# 5v_to_3_3v_convertor.net
KiCad netlist of a schematic drawn in Altium Designer
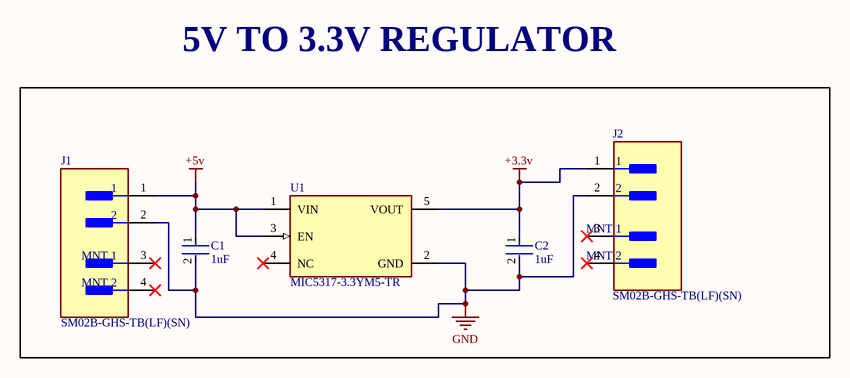
[diagram p0: 5v to 3.3v convertor.SchDoc]

(export (version "E")
  (design (tool "Eeschema 10.0.6"))
  (components
    (comp (ref "C1")
      (value "1uF")
      (footprint "FP-CC0805-0_85-MFG")
      (description "CAP CER 1UF 10V X7R 0805")
      (fields
        (field (name "MANUFACTURER") "Yageo")
        (field (name "OCTOPART") "https://octopart.com/cc0805kkx7r6bb105-yageo-42522859")
      )
      (libsource (lib "Altium Content Vault") (part "11868f565c42a9108669ba33697ecf6"))
    )
    (comp (ref "C2")
      (value "1uF")
      (footprint "FP-CC0805-0_85-MFG")
      (description "CAP CER 1UF 10V X7R 0805")
      (fields
        (field (name "MANUFACTURER") "Yageo")
        (field (name "OCTOPART") "https://octopart.com/cc0805kkx7r6bb105-yageo-42522859")
      )
      (libsource (lib "Altium Content Vault") (part "11868f565c42a9108669ba33697ecf6"))
    )
    (comp (ref "J1")
      (value "SM02B-GHS-TB(LF)(SN)")
      (footprint "FP-SM02B-GHS-TB_LF_SN-MFG")
      (description "CONN HEADER SMD R/A 2POS 1.25MM")
      (libsource (lib "Altium Content Vault") (part "56ec3178a87b3978bdc1b3682cd516a"))
    )
    (comp (ref "J2")
      (value "SM02B-GHS-TB(LF)(SN)")
      (footprint "FP-SM02B-GHS-TB_LF_SN-MFG")
      (description "CONN HEADER SMD R/A 2POS 1.25MM")
      (libsource (lib "") (part "56ec3178a87b3978bdc1b3682cd516a_1"))
    )
    (comp (ref "U1")
      (value "MIC5317-3.3YM5-TR")
      (footprint "FP-SOT23-5LD-PL-1-MFG")
      (description "IC REG LINEAR 3.3V 150MA SOT23-5")
      (libsource (lib "Altium Content Vault") (part "0a093dae7315cdc977fd108dde87457"))
    )
  )
  (nets
    (net (code "1") (name "+3.3v") (class "Default")
      (node (ref "C2") (pin "1") (pinfunction "1_1") (pintype "passive"))
      (node (ref "J2") (pin "1") (pinfunction "1_1") (pintype "passive"))
      (node (ref "U1") (pin "5") (pinfunction "VOUT_5") (pintype "power_in"))
    )
    (net (code "2") (name "+5v") (class "Default")
      (node (ref "C1") (pin "1") (pinfunction "1_1") (pintype "passive"))
      (node (ref "J1") (pin "1") (pinfunction "1_1") (pintype "passive"))
      (node (ref "U1") (pin "1") (pinfunction "VIN_1") (pintype "power_in"))
      (node (ref "U1") (pin "3") (pinfunction "EN_3") (pintype "input"))
    )
    (net (code "3") (name "GND") (class "Default")
      (node (ref "C1") (pin "2") (pinfunction "2_2") (pintype "passive"))
      (node (ref "C2") (pin "2") (pinfunction "2_2") (pintype "passive"))
      (node (ref "J1") (pin "2") (pinfunction "2_2") (pintype "passive"))
      (node (ref "J2") (pin "2") (pinfunction "2_2") (pintype "passive"))
      (node (ref "U1") (pin "2") (pinfunction "GND_2") (pintype "power_in"))
    )
    (net (code "4") (name "unconnected-(J1-MNT_1-Pad3)") (class "Default")
      (node (ref "J1") (pin "3") (pinfunction "MNT_1_3") (pintype "passive+no_connect"))
    )
    (net (code "5") (name "unconnected-(J1-MNT_2-Pad4)") (class "Default")
      (node (ref "J1") (pin "4") (pinfunction "MNT_2_4") (pintype "passive+no_connect"))
    )
    (net (code "6") (name "unconnected-(J2-MNT_1-Pad3)") (class "Default")
      (node (ref "J2") (pin "3") (pinfunction "MNT_1_3") (pintype "passive+no_connect"))
    )
    (net (code "7") (name "unconnected-(J2-MNT_2-Pad4)") (class "Default")
      (node (ref "J2") (pin "4") (pinfunction "MNT_2_4") (pintype "passive+no_connect"))
    )
    (net (code "8") (name "unconnected-(U1-NC-Pad4)") (class "Default")
      (node (ref "U1") (pin "4") (pinfunction "NC_4") (pintype "passive+no_connect"))
    )
  )
)
